# YoctoBob_LPC1102.net
KiCad netlist of a schematic drawn in Altium Designer
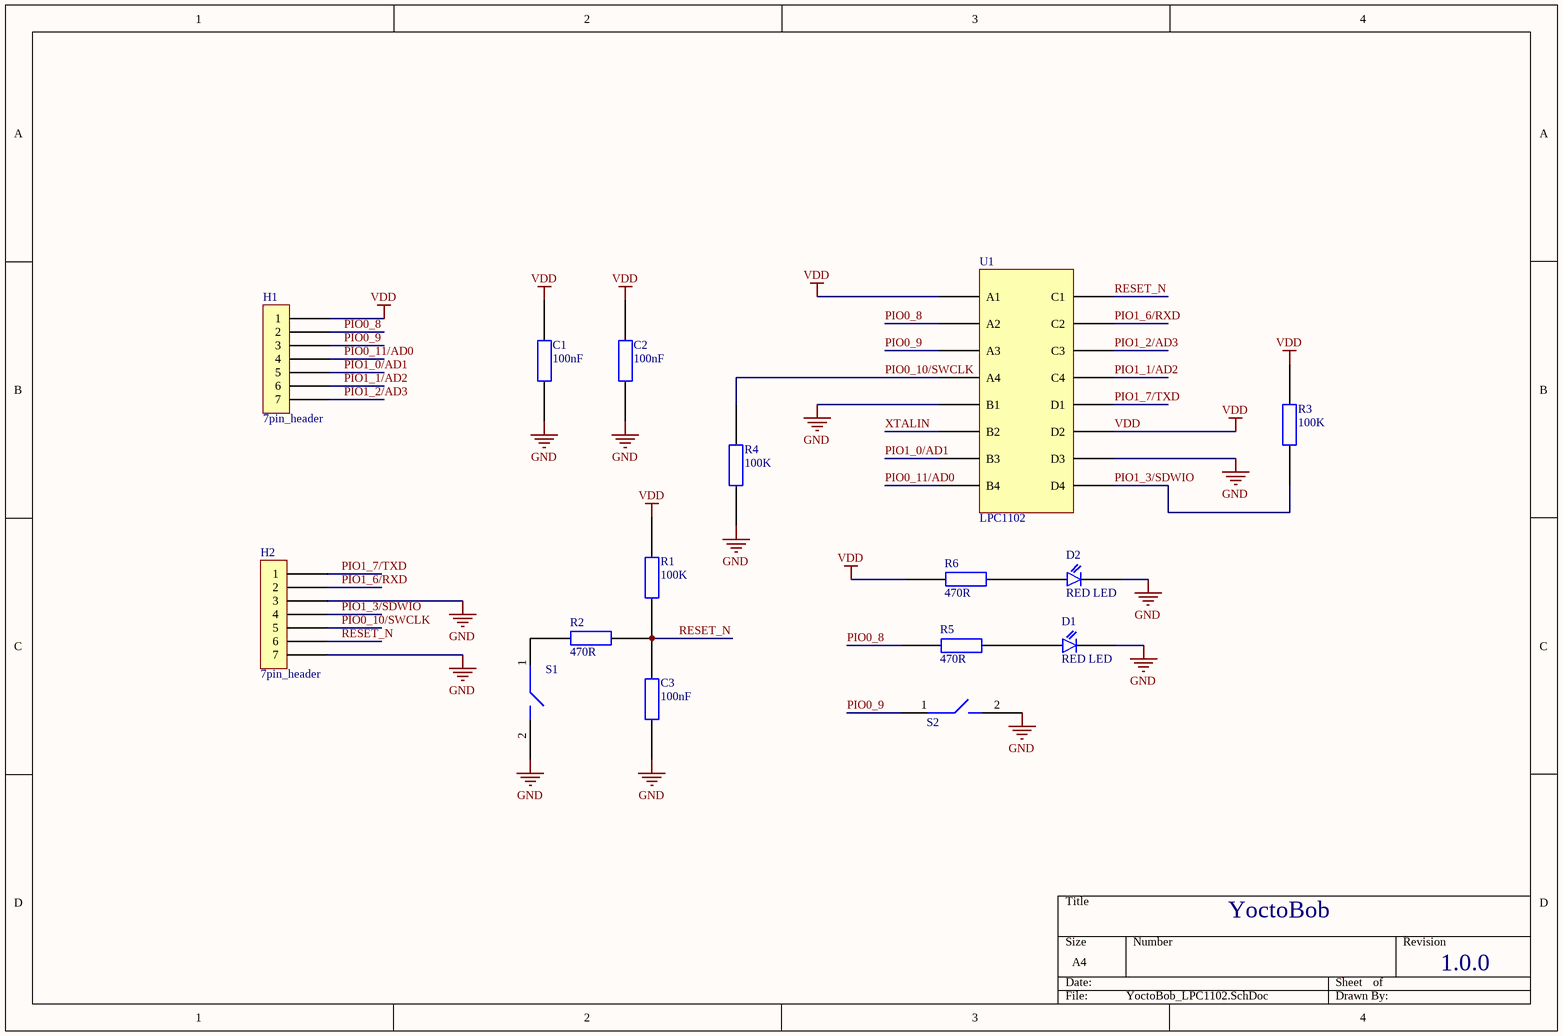
[diagram p0: YoctoBob_LPC1102.SchDoc]

(export (version "E")
  (design (tool "Eeschema 10.0.6"))
  (components
    (comp (ref "C1") (value "100nF") (footprint "C0805") (libsource (lib "Component_Library") (part "100nF")))
    (comp (ref "C2") (value "100nF") (footprint "C0805") (libsource (lib "Component_Library") (part "100nF")))
    (comp (ref "C3") (value "100nF") (footprint "C0805") (libsource (lib "Component_Library") (part "100nF")))
    (comp (ref "D1")
      (value "RED LED")
      (footprint "RED_LED_0805")
      (libsource (lib "Component_Library") (part "RED LED"))
    )
    (comp (ref "D2")
      (value "RED LED")
      (footprint "RED_LED_0805")
      (libsource (lib "Component_Library") (part "RED LED"))
    )
    (comp (ref "H1")
      (value "7pin_header")
      (footprint "7POS_HEADER")
      (libsource (lib "Component_Library") (part "7pin_header"))
    )
    (comp (ref "H2")
      (value "7pin_header")
      (footprint "7POS_HEADER")
      (libsource (lib "Component_Library") (part "7pin_header"))
    )
    (comp (ref "R1") (value "100K") (footprint "R0805") (libsource (lib "Component_Library") (part "100K")))
    (comp (ref "R2") (value "470R") (footprint "R0805") (libsource (lib "Component_Library") (part "470R")))
    (comp (ref "R3") (value "100K") (footprint "R0805") (libsource (lib "Component_Library") (part "100K")))
    (comp (ref "R4") (value "100K") (footprint "R0805") (libsource (lib "Component_Library") (part "100K")))
    (comp (ref "R5") (value "470R") (footprint "R0805") (libsource (lib "Component_Library") (part "470R")))
    (comp (ref "R6") (value "470R") (footprint "R0805") (libsource (lib "Component_Library") (part "470R")))
    (comp (ref "S1")
      (value "switch")
      (footprint "SWITCH_B3U-1000P")
      (libsource (lib "Component_Library") (part "switch"))
    )
    (comp (ref "S2")
      (value "switch")
      (footprint "SWITCH_B3U-1000P")
      (libsource (lib "Component_Library") (part "switch"))
    )
    (comp (ref "U1")
      (value "LPC1102")
      (footprint "BGA16x4")
      (libsource (lib "Component_Library") (part "LPC1102"))
    )
  )
  (nets
    (net (code "1") (name "/PIO0_8") (class "Default")
      (node (ref "H1") (pin "2") (pinfunction "2_2") (pintype "passive"))
      (node (ref "R5") (pin "1") (pinfunction "1_1") (pintype "passive"))
      (node (ref "U1") (pin "A2") (pinfunction "A2_A2") (pintype "passive"))
    )
    (net (code "2") (name "/PIO0_9") (class "Default")
      (node (ref "H1") (pin "3") (pinfunction "3_3") (pintype "passive"))
      (node (ref "S2") (pin "1") (pinfunction "1_1") (pintype "passive"))
      (node (ref "U1") (pin "A3") (pinfunction "A3_A3") (pintype "passive"))
    )
    (net (code "3") (name "/PIO0_10{slash}SWCLK") (class "Default")
      (node (ref "H2") (pin "5") (pinfunction "5_5") (pintype "passive"))
      (node (ref "R4") (pin "1") (pinfunction "1_1") (pintype "passive"))
      (node (ref "U1") (pin "A4") (pinfunction "A4_A4") (pintype "passive"))
    )
    (net (code "4") (name "/PIO0_11{slash}AD0") (class "Default")
      (node (ref "H1") (pin "4") (pinfunction "4_4") (pintype "passive"))
      (node (ref "U1") (pin "B4") (pinfunction "B4_B4") (pintype "passive"))
    )
    (net (code "5") (name "/PIO1_0{slash}AD1") (class "Default")
      (node (ref "H1") (pin "5") (pinfunction "5_5") (pintype "passive"))
      (node (ref "U1") (pin "B3") (pinfunction "B3_B3") (pintype "passive"))
    )
    (net (code "6") (name "/PIO1_1{slash}AD2") (class "Default")
      (node (ref "H1") (pin "6") (pinfunction "6_6") (pintype "passive"))
      (node (ref "U1") (pin "C4") (pinfunction "C4_C4") (pintype "passive"))
    )
    (net (code "7") (name "/PIO1_2{slash}AD3") (class "Default")
      (node (ref "H1") (pin "7") (pinfunction "7_7") (pintype "passive"))
      (node (ref "U1") (pin "C3") (pinfunction "C3_C3") (pintype "passive"))
    )
    (net (code "8") (name "/PIO1_3{slash}SDWIO") (class "Default")
      (node (ref "H2") (pin "4") (pinfunction "4_4") (pintype "passive"))
      (node (ref "R3") (pin "2") (pinfunction "2_2") (pintype "passive"))
      (node (ref "U1") (pin "D4") (pinfunction "D4_D4") (pintype "passive"))
    )
    (net (code "9") (name "/PIO1_6{slash}RXD") (class "Default")
      (node (ref "H2") (pin "2") (pinfunction "2_2") (pintype "passive"))
      (node (ref "U1") (pin "C2") (pinfunction "C2_C2") (pintype "passive"))
    )
    (net (code "10") (name "/PIO1_7{slash}TXD") (class "Default")
      (node (ref "H2") (pin "1") (pinfunction "1_1") (pintype "passive"))
      (node (ref "U1") (pin "D1") (pinfunction "D1_D1") (pintype "passive"))
    )
    (net (code "11") (name "/RESET_N") (class "Default")
      (node (ref "C3") (pin "2") (pinfunction "2_2") (pintype "passive"))
      (node (ref "H2") (pin "6") (pinfunction "6_6") (pintype "passive"))
      (node (ref "R1") (pin "1") (pinfunction "1_1") (pintype "passive"))
      (node (ref "R2") (pin "2") (pinfunction "2_2") (pintype "passive"))
      (node (ref "U1") (pin "C1") (pinfunction "C1_C1") (pintype "passive"))
    )
    (net (code "12") (name "/XTALIN") (class "Default")
      (node (ref "U1") (pin "B2") (pinfunction "B2_B2") (pintype "passive"))
    )
    (net (code "13") (name "GND") (class "Default")
      (node (ref "C1") (pin "1") (pinfunction "1_1") (pintype "passive"))
      (node (ref "C2") (pin "1") (pinfunction "1_1") (pintype "passive"))
      (node (ref "C3") (pin "1") (pinfunction "1_1") (pintype "passive"))
      (node (ref "D1") (pin "2") (pinfunction "2_2") (pintype "passive"))
      (node (ref "D2") (pin "2") (pinfunction "2_2") (pintype "passive"))
      (node (ref "H2") (pin "3") (pinfunction "3_3") (pintype "passive"))
      (node (ref "H2") (pin "7") (pinfunction "7_7") (pintype "passive"))
      (node (ref "R4") (pin "2") (pinfunction "2_2") (pintype "passive"))
      (node (ref "S1") (pin "2") (pinfunction "2_2") (pintype "passive"))
      (node (ref "S2") (pin "2") (pinfunction "2_2") (pintype "passive"))
      (node (ref "U1") (pin "B1") (pinfunction "B1_B1") (pintype "passive"))
      (node (ref "U1") (pin "D3") (pinfunction "D3_D3") (pintype "passive"))
    )
    (net (code "14") (name "Net-(D1-Pad1)") (class "Default")
      (node (ref "D1") (pin "1") (pinfunction "1_1") (pintype "passive"))
      (node (ref "R5") (pin "2") (pinfunction "2_2") (pintype "passive"))
    )
    (net (code "15") (name "Net-(D2-Pad1)") (class "Default")
      (node (ref "D2") (pin "1") (pinfunction "1_1") (pintype "passive"))
      (node (ref "R6") (pin "2") (pinfunction "2_2") (pintype "passive"))
    )
    (net (code "16") (name "Net-(R2-Pad1)") (class "Default")
      (node (ref "R2") (pin "1") (pinfunction "1_1") (pintype "passive"))
      (node (ref "S1") (pin "1") (pinfunction "1_1") (pintype "passive"))
    )
    (net (code "17") (name "VDD") (class "Default")
      (node (ref "C1") (pin "2") (pinfunction "2_2") (pintype "passive"))
      (node (ref "C2") (pin "2") (pinfunction "2_2") (pintype "passive"))
      (node (ref "H1") (pin "1") (pinfunction "1_1") (pintype "passive"))
      (node (ref "R1") (pin "2") (pinfunction "2_2") (pintype "passive"))
      (node (ref "R3") (pin "1") (pinfunction "1_1") (pintype "passive"))
      (node (ref "R6") (pin "1") (pinfunction "1_1") (pintype "passive"))
      (node (ref "U1") (pin "A1") (pinfunction "A1_A1") (pintype "passive"))
      (node (ref "U1") (pin "D2") (pinfunction "D2_D2") (pintype "passive"))
    )
  )
)
